# Adapter.net
KiCad netlist of a schematic drawn in EAGLE
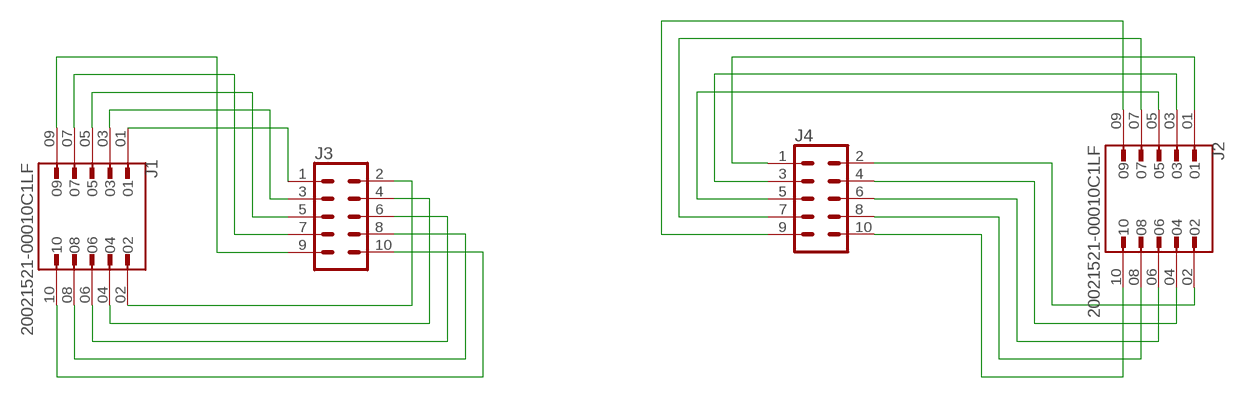
[diagram p0: schematic, sheet 1]

(export (version "E")
  (design (tool "Eeschema 10.0.6"))
  (components
    (comp (ref "J1")
      (value "20021521-00010C1LF")
      (footprint "eagle-import:AMPHENOL_20021521-00010C1LF")
      (fields (field (name "MF") "AMPHENOL ICC / FCI"))
      (libsource (lib "eagle-import") (part "20021521-00010C1LF"))
    )
    (comp (ref "J2")
      (value "20021521-00010C1LF")
      (footprint "eagle-import:AMPHENOL_20021521-00010C1LF")
      (fields (field (name "MF") "AMPHENOL ICC / FCI"))
      (libsource (lib "eagle-import") (part "20021521-00010C1LF"))
    )
    (comp (ref "J3")
      (value "CONN_05X2NO_SILK")
      (footprint "eagle-import:2X5_NOSILK")
      (libsource (lib "eagle-import") (part "CONN_05X2NO_SILK"))
    )
    (comp (ref "J4")
      (value "CONN_05X2NO_SILK")
      (footprint "eagle-import:2X5_NOSILK")
      (libsource (lib "eagle-import") (part "CONN_05X2NO_SILK"))
    )
  )
  (nets
    (net (code "1") (name "Net-(J1-Pad01)") (class "Default")
      (node (ref "J1") (pin "01") (pinfunction "01_01") (pintype "passive"))
      (node (ref "J3") (pin "1") (pinfunction "1_1") (pintype "passive"))
    )
    (net (code "2") (name "Net-(J1-Pad02)") (class "Default")
      (node (ref "J1") (pin "02") (pinfunction "02_02") (pintype "passive"))
      (node (ref "J3") (pin "2") (pinfunction "2_2") (pintype "passive"))
    )
    (net (code "3") (name "Net-(J1-Pad03)") (class "Default")
      (node (ref "J1") (pin "03") (pinfunction "03_03") (pintype "passive"))
      (node (ref "J3") (pin "3") (pinfunction "3_3") (pintype "passive"))
    )
    (net (code "4") (name "Net-(J1-Pad04)") (class "Default")
      (node (ref "J1") (pin "04") (pinfunction "04_04") (pintype "passive"))
      (node (ref "J3") (pin "4") (pinfunction "4_4") (pintype "passive"))
    )
    (net (code "5") (name "Net-(J1-Pad05)") (class "Default")
      (node (ref "J1") (pin "05") (pinfunction "05_05") (pintype "passive"))
      (node (ref "J3") (pin "5") (pinfunction "5_5") (pintype "passive"))
    )
    (net (code "6") (name "Net-(J1-Pad06)") (class "Default")
      (node (ref "J1") (pin "06") (pinfunction "06_06") (pintype "passive"))
      (node (ref "J3") (pin "6") (pinfunction "6_6") (pintype "passive"))
    )
    (net (code "7") (name "Net-(J1-Pad07)") (class "Default")
      (node (ref "J1") (pin "07") (pinfunction "07_07") (pintype "passive"))
      (node (ref "J3") (pin "7") (pinfunction "7_7") (pintype "passive"))
    )
    (net (code "8") (name "Net-(J1-Pad08)") (class "Default")
      (node (ref "J1") (pin "08") (pinfunction "08_08") (pintype "passive"))
      (node (ref "J3") (pin "8") (pinfunction "8_8") (pintype "passive"))
    )
    (net (code "9") (name "Net-(J1-Pad09)") (class "Default")
      (node (ref "J1") (pin "09") (pinfunction "09_09") (pintype "passive"))
      (node (ref "J3") (pin "9") (pinfunction "9_9") (pintype "passive"))
    )
    (net (code "10") (name "Net-(J1-Pad10)") (class "Default")
      (node (ref "J1") (pin "10") (pinfunction "10_10") (pintype "passive"))
      (node (ref "J3") (pin "10") (pinfunction "10_10") (pintype "passive"))
    )
    (net (code "11") (name "Net-(J2-Pad01)") (class "Default")
      (node (ref "J2") (pin "01") (pinfunction "01_01") (pintype "passive"))
      (node (ref "J4") (pin "1") (pinfunction "1_1") (pintype "passive"))
    )
    (net (code "12") (name "Net-(J2-Pad02)") (class "Default")
      (node (ref "J2") (pin "02") (pinfunction "02_02") (pintype "passive"))
      (node (ref "J4") (pin "2") (pinfunction "2_2") (pintype "passive"))
    )
    (net (code "13") (name "Net-(J2-Pad03)") (class "Default")
      (node (ref "J2") (pin "03") (pinfunction "03_03") (pintype "passive"))
      (node (ref "J4") (pin "3") (pinfunction "3_3") (pintype "passive"))
    )
    (net (code "14") (name "Net-(J2-Pad04)") (class "Default")
      (node (ref "J2") (pin "04") (pinfunction "04_04") (pintype "passive"))
      (node (ref "J4") (pin "4") (pinfunction "4_4") (pintype "passive"))
    )
    (net (code "15") (name "Net-(J2-Pad05)") (class "Default")
      (node (ref "J2") (pin "05") (pinfunction "05_05") (pintype "passive"))
      (node (ref "J4") (pin "5") (pinfunction "5_5") (pintype "passive"))
    )
    (net (code "16") (name "Net-(J2-Pad06)") (class "Default")
      (node (ref "J2") (pin "06") (pinfunction "06_06") (pintype "passive"))
      (node (ref "J4") (pin "6") (pinfunction "6_6") (pintype "passive"))
    )
    (net (code "17") (name "Net-(J2-Pad07)") (class "Default")
      (node (ref "J2") (pin "07") (pinfunction "07_07") (pintype "passive"))
      (node (ref "J4") (pin "7") (pinfunction "7_7") (pintype "passive"))
    )
    (net (code "18") (name "Net-(J2-Pad08)") (class "Default")
      (node (ref "J2") (pin "08") (pinfunction "08_08") (pintype "passive"))
      (node (ref "J4") (pin "8") (pinfunction "8_8") (pintype "passive"))
    )
    (net (code "19") (name "Net-(J2-Pad09)") (class "Default")
      (node (ref "J2") (pin "09") (pinfunction "09_09") (pintype "passive"))
      (node (ref "J4") (pin "9") (pinfunction "9_9") (pintype "passive"))
    )
    (net (code "20") (name "Net-(J2-Pad10)") (class "Default")
      (node (ref "J2") (pin "10") (pinfunction "10_10") (pintype "passive"))
      (node (ref "J4") (pin "10") (pinfunction "10_10") (pintype "passive"))
    )
  )
)
